# Light_sensor_multi_si11xx_veml6070.net
KiCad netlist of a schematic drawn in EAGLE
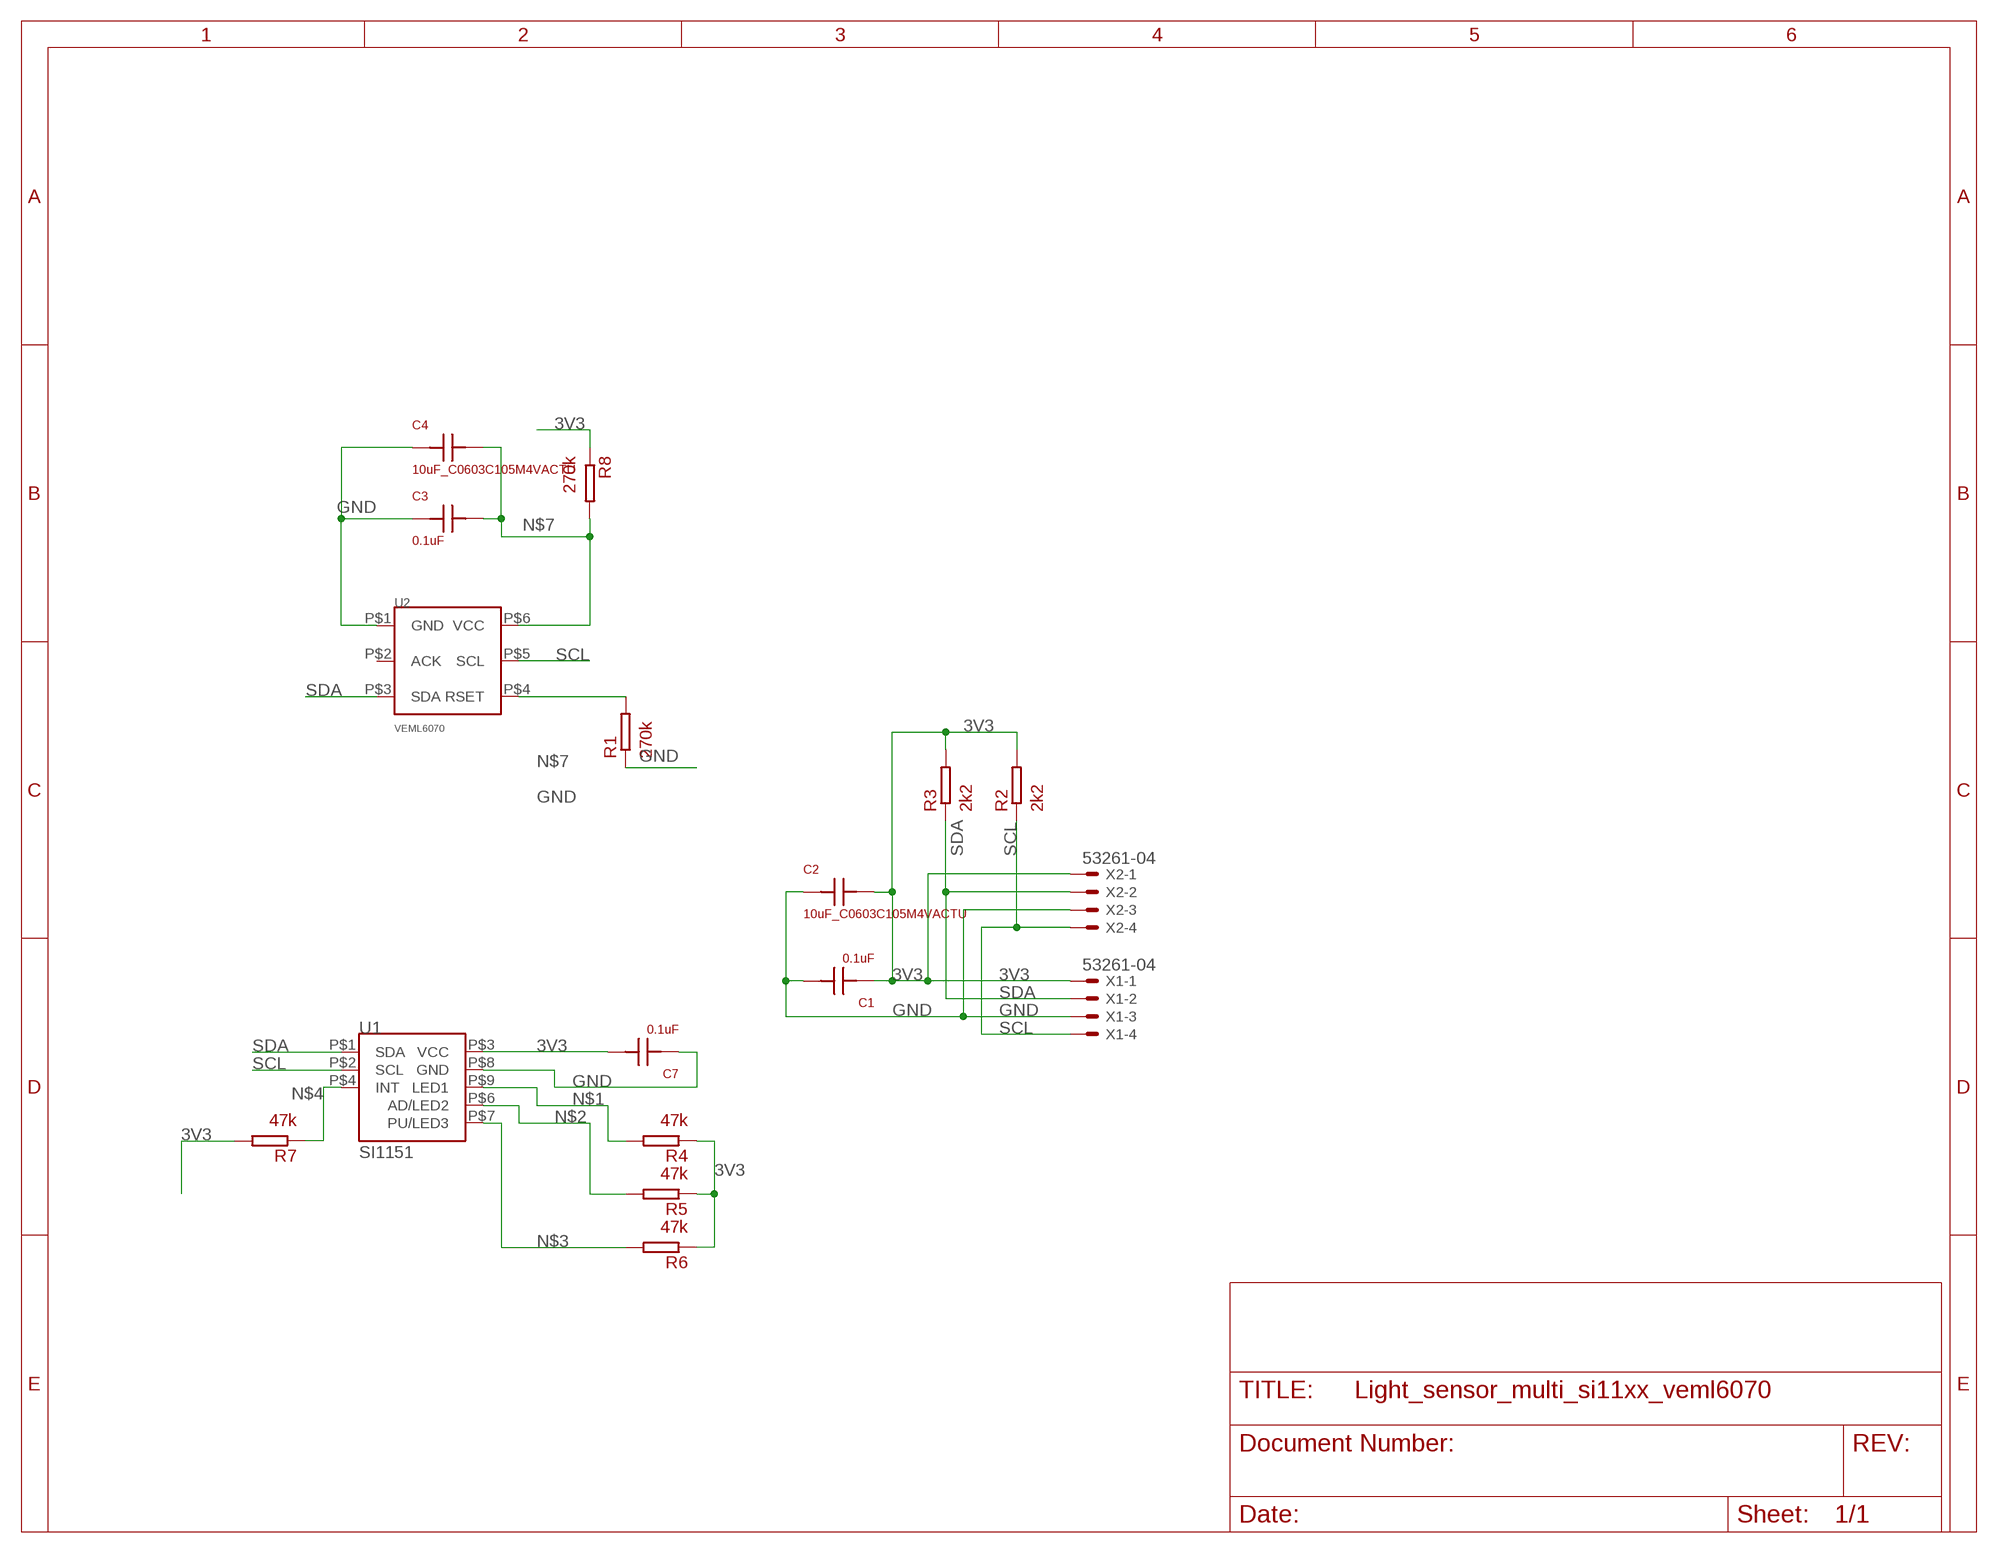
[diagram p0: schematic, sheet 1]

(export (version "E")
  (design (tool "Eeschema 10.0.6"))
  (components
    (comp (ref "C1")
      (value "0.1uF")
      (footprint "eagle-import:SMD_0402")
      (libsource (lib "eagle-import") (part "CAP_NP_0402"))
    )
    (comp (ref "C2")
      (value "10uF_C0603C105M4VACTU")
      (footprint "eagle-import:SMD_1206")
      (libsource (lib "eagle-import") (part "CAP_NP_1206"))
    )
    (comp (ref "C3")
      (value "0.1uF")
      (footprint "eagle-import:SMD_0402")
      (libsource (lib "eagle-import") (part "CAP_NP_0402"))
    )
    (comp (ref "C4")
      (value "10uF_C0603C105M4VACTU")
      (footprint "eagle-import:SMD_1206")
      (libsource (lib "eagle-import") (part "CAP_NP_1206"))
    )
    (comp (ref "C7")
      (value "0.1uF")
      (footprint "eagle-import:SMD_0402")
      (libsource (lib "eagle-import") (part "CAP_NP_0402"))
    )
    (comp (ref "R1")
      (value "270k")
      (footprint "eagle-import:SMD_0402")
      (libsource (lib "eagle-import") (part "RESISTOR_0402"))
    )
    (comp (ref "R2")
      (value "2k2")
      (footprint "eagle-import:SMD_0402")
      (libsource (lib "eagle-import") (part "RESISTOR_0402"))
    )
    (comp (ref "R3")
      (value "2k2")
      (footprint "eagle-import:SMD_0402")
      (libsource (lib "eagle-import") (part "RESISTOR_0402"))
    )
    (comp (ref "R4")
      (value "47k")
      (footprint "eagle-import:SMD_0402")
      (libsource (lib "eagle-import") (part "RESISTOR_0402"))
    )
    (comp (ref "R5")
      (value "47k")
      (footprint "eagle-import:SMD_0402")
      (libsource (lib "eagle-import") (part "RESISTOR_0402"))
    )
    (comp (ref "R6")
      (value "47k")
      (footprint "eagle-import:SMD_0402")
      (libsource (lib "eagle-import") (part "RESISTOR_0402"))
    )
    (comp (ref "R7")
      (value "47k")
      (footprint "eagle-import:SMD_0402")
      (libsource (lib "eagle-import") (part "RESISTOR_0402"))
    )
    (comp (ref "R8")
      (value "270k")
      (footprint "eagle-import:SMD_0402")
      (libsource (lib "eagle-import") (part "RESISTOR_0402"))
    )
    (comp (ref "U1")
      (value "SI1151")
      (footprint "eagle-import:QFN10")
      (libsource (lib "eagle-import") (part "SI1151_AB00_DFN10"))
    )
    (comp (ref "U2")
      (value "VEML6070")
      (footprint "eagle-import:OPLGA-6")
      (libsource (lib "eagle-import") (part "VEML6070_OPLGA"))
    )
    (comp (ref "X1")
      (value "53261-04")
      (footprint "eagle-import:53261-04")
      (fields (field (name "MF") "MOLEX"))
      (libsource (lib "eagle-import") (part "53?-04261"))
    )
    (comp (ref "X2")
      (value "53261-04")
      (footprint "eagle-import:53261-04")
      (fields (field (name "MF") "MOLEX"))
      (libsource (lib "eagle-import") (part "53?-04261"))
    )
  )
  (nets
    (net (code "1") (name "/3V3") (class "Default")
      (node (ref "C1") (pin "P$1") (pinfunction "P$1_P$1") (pintype "passive"))
      (node (ref "C2") (pin "P$2") (pinfunction "P$2_P$2") (pintype "passive"))
      (node (ref "C7") (pin "P$2") (pinfunction "P$2_P$2") (pintype "passive"))
      (node (ref "R2") (pin "P$2") (pinfunction "P$2_P$2") (pintype "passive"))
      (node (ref "R3") (pin "P$2") (pinfunction "P$2_P$2") (pintype "passive"))
      (node (ref "R4") (pin "P$1") (pinfunction "P$1_P$1") (pintype "passive"))
      (node (ref "R5") (pin "P$1") (pinfunction "P$1_P$1") (pintype "passive"))
      (node (ref "R6") (pin "P$1") (pinfunction "P$1_P$1") (pintype "passive"))
      (node (ref "R7") (pin "P$2") (pinfunction "P$2_P$2") (pintype "passive"))
      (node (ref "R8") (pin "P$1") (pinfunction "P$1_P$1") (pintype "passive"))
      (node (ref "U1") (pin "P$3") (pinfunction "VCC_P$3") (pintype "power_in"))
      (node (ref "X1") (pin "1") (pinfunction "S_1") (pintype "passive"))
      (node (ref "X2") (pin "1") (pinfunction "S_1") (pintype "passive"))
    )
    (net (code "2") (name "/GND") (class "Default")
      (node (ref "C1") (pin "P$2") (pinfunction "P$2_P$2") (pintype "passive"))
      (node (ref "C2") (pin "P$1") (pinfunction "P$1_P$1") (pintype "passive"))
      (node (ref "C3") (pin "P$1") (pinfunction "P$1_P$1") (pintype "passive"))
      (node (ref "C4") (pin "P$1") (pinfunction "P$1_P$1") (pintype "passive"))
      (node (ref "C7") (pin "P$1") (pinfunction "P$1_P$1") (pintype "passive"))
      (node (ref "R1") (pin "P$1") (pinfunction "P$1_P$1") (pintype "passive"))
      (node (ref "U1") (pin "P$8") (pinfunction "GND_P$8") (pintype "power_in"))
      (node (ref "U2") (pin "P$1") (pinfunction "GND_P$1") (pintype "power_in"))
      (node (ref "X1") (pin "3") (pinfunction "S_3") (pintype "passive"))
      (node (ref "X2") (pin "3") (pinfunction "S_3") (pintype "passive"))
    )
    (net (code "3") (name "/N$1") (class "Default")
      (node (ref "R4") (pin "P$2") (pinfunction "P$2_P$2") (pintype "passive"))
      (node (ref "U1") (pin "P$9") (pinfunction "LED1_P$9") (pintype "output"))
    )
    (net (code "4") (name "/N$2") (class "Default")
      (node (ref "R5") (pin "P$2") (pinfunction "P$2_P$2") (pintype "passive"))
      (node (ref "U1") (pin "P$6") (pinfunction "AD/LED2_P$6") (pintype "input"))
    )
    (net (code "5") (name "/N$3") (class "Default")
      (node (ref "R6") (pin "P$2") (pinfunction "P$2_P$2") (pintype "passive"))
      (node (ref "U1") (pin "P$7") (pinfunction "PU/LED3_P$7") (pintype "input"))
    )
    (net (code "6") (name "/N$4") (class "Default")
      (node (ref "R7") (pin "P$1") (pinfunction "P$1_P$1") (pintype "passive"))
      (node (ref "U1") (pin "P$4") (pinfunction "INT_P$4") (pintype "output"))
    )
    (net (code "7") (name "/N$7") (class "Default")
      (node (ref "C3") (pin "P$2") (pinfunction "P$2_P$2") (pintype "passive"))
      (node (ref "C4") (pin "P$2") (pinfunction "P$2_P$2") (pintype "passive"))
      (node (ref "R8") (pin "P$2") (pinfunction "P$2_P$2") (pintype "passive"))
      (node (ref "U2") (pin "P$6") (pinfunction "VCC_P$6") (pintype "power_in"))
    )
    (net (code "8") (name "/SCL") (class "Default")
      (node (ref "R2") (pin "P$1") (pinfunction "P$1_P$1") (pintype "passive"))
      (node (ref "U1") (pin "P$2") (pinfunction "SCL_P$2") (pintype "bidirectional"))
      (node (ref "U2") (pin "P$5") (pinfunction "SCL_P$5") (pintype "input"))
      (node (ref "X1") (pin "4") (pinfunction "S_4") (pintype "passive"))
      (node (ref "X2") (pin "4") (pinfunction "S_4") (pintype "passive"))
    )
    (net (code "9") (name "/SDA") (class "Default")
      (node (ref "R3") (pin "P$1") (pinfunction "P$1_P$1") (pintype "passive"))
      (node (ref "U1") (pin "P$1") (pinfunction "SDA_P$1") (pintype "bidirectional"))
      (node (ref "U2") (pin "P$3") (pinfunction "SDA_P$3") (pintype "bidirectional"))
      (node (ref "X1") (pin "2") (pinfunction "S_2") (pintype "passive"))
      (node (ref "X2") (pin "2") (pinfunction "S_2") (pintype "passive"))
    )
    (net (code "10") (name "Net-(U2-RSET)") (class "Default")
      (node (ref "R1") (pin "P$2") (pinfunction "P$2_P$2") (pintype "passive"))
      (node (ref "U2") (pin "P$4") (pinfunction "RSET_P$4") (pintype "passive"))
    )
    (net (code "11") (name "unconnected-(U2-ACK-PadP$2)") (class "Default")
      (node (ref "U2") (pin "P$2") (pinfunction "ACK_P$2") (pintype "output"))
    )
  )
)
